# Water_Leak_Detector_PCB.net
KiCad netlist of a schematic drawn in EAGLE
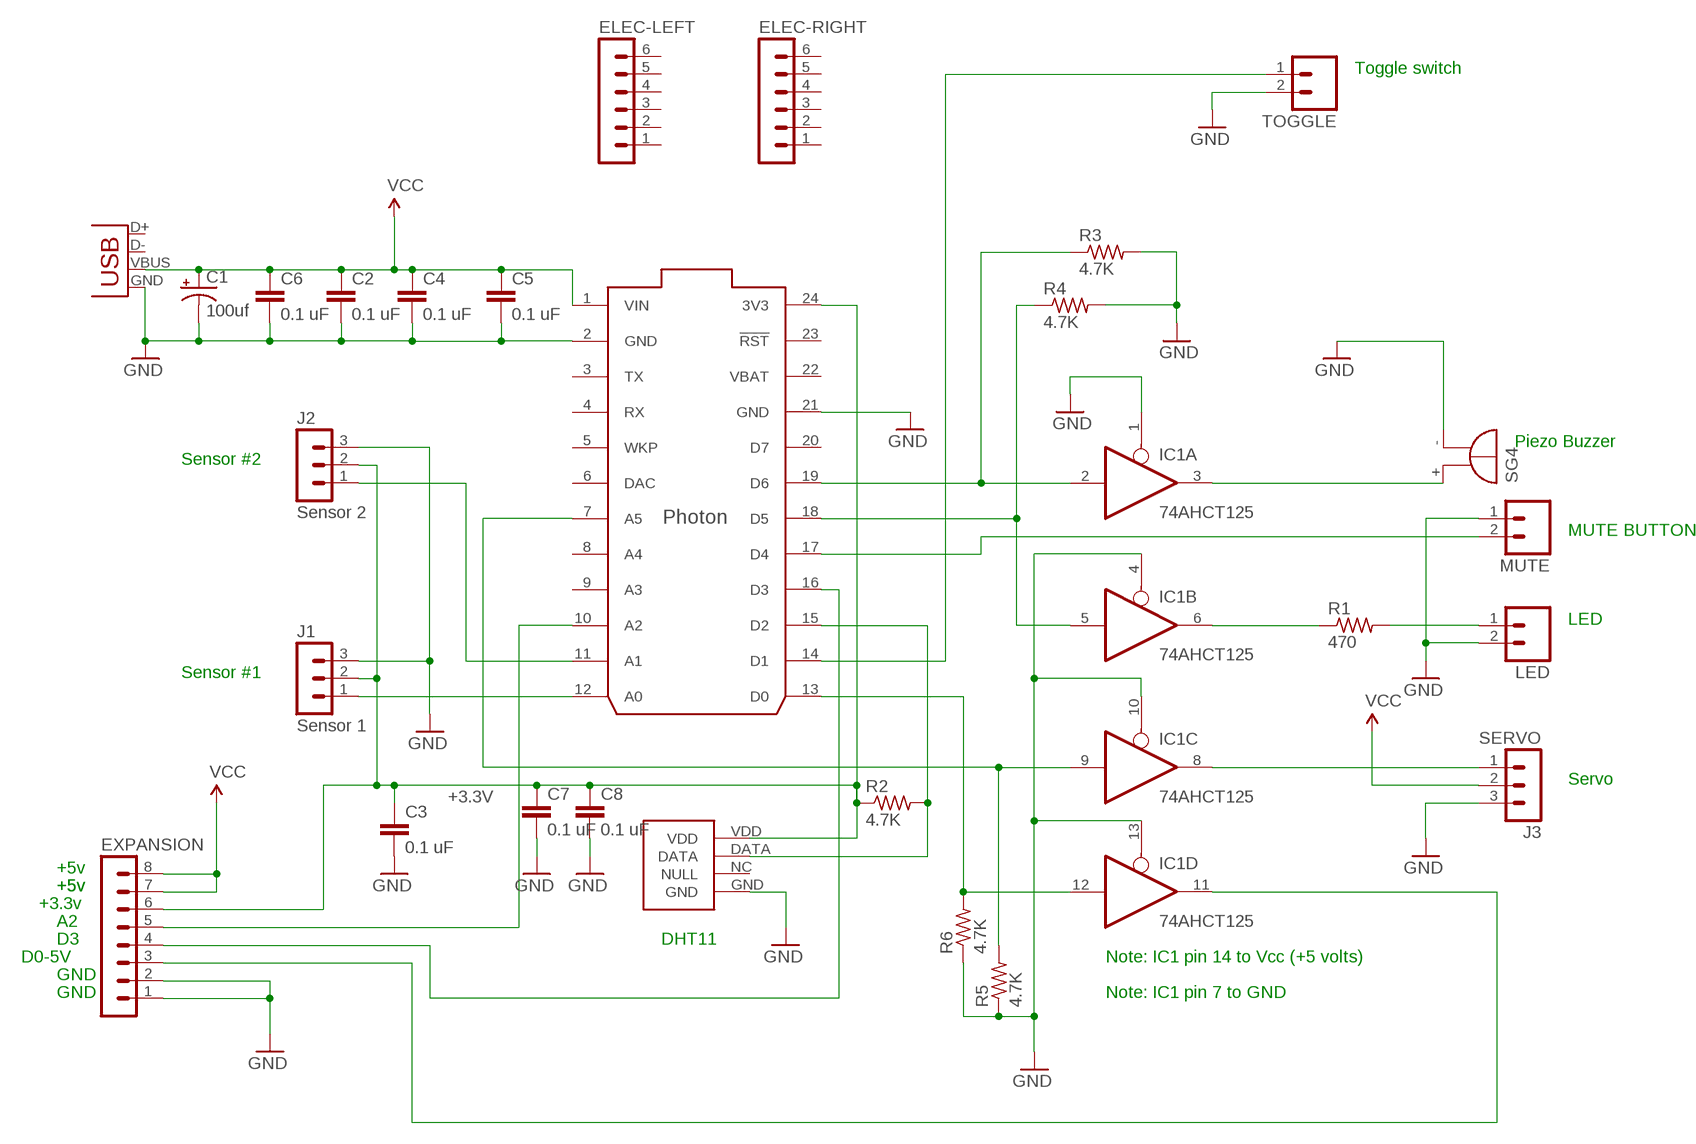
[diagram p0: schematic, sheet 1]

(export (version "E")
  (design (tool "Eeschema 10.0.6"))
  (components
    (comp (ref "C1")
      (value "100uf")
      (footprint "eagle-import:CPOL-RADIAL-100UF-25V")
      (libsource (lib "eagle-import") (part "CAP_POLPTH1"))
    )
    (comp (ref "C2")
      (value "0.1 uF")
      (footprint "eagle-import:CAP-PTH-SMALL")
      (libsource (lib "eagle-import") (part "CAPPTH"))
    )
    (comp (ref "C3")
      (value "0.1 uF")
      (footprint "eagle-import:CAP-PTH-SMALL")
      (libsource (lib "eagle-import") (part "CAPPTH"))
    )
    (comp (ref "C4")
      (value "0.1 uF")
      (footprint "eagle-import:CAP-PTH-SMALL")
      (libsource (lib "eagle-import") (part "CAPPTH"))
    )
    (comp (ref "C5")
      (value "0.1 uF")
      (footprint "eagle-import:CAP-PTH-SMALL")
      (libsource (lib "eagle-import") (part "CAPPTH"))
    )
    (comp (ref "C6")
      (value "0.1 uF")
      (footprint "eagle-import:CAP-PTH-SMALL")
      (libsource (lib "eagle-import") (part "CAPPTH"))
    )
    (comp (ref "C7")
      (value "0.1 uF")
      (footprint "eagle-import:CAP-PTH-SMALL")
      (libsource (lib "eagle-import") (part "CAPPTH"))
    )
    (comp (ref "C8")
      (value "0.1 uF")
      (footprint "eagle-import:CAP-PTH-SMALL")
      (libsource (lib "eagle-import") (part "CAPPTH"))
    )
    (comp (ref "ELEC-LEFT")
      (value "MA06-1")
      (footprint "eagle-import:MA06-1")
      (libsource (lib "eagle-import") (part "MA06-1"))
    )
    (comp (ref "ELEC-RIGHT")
      (value "MA06-1")
      (footprint "eagle-import:MA06-1")
      (libsource (lib "eagle-import") (part "MA06-1"))
    )
    (comp (ref "EXPANSION")
      (value "MA08-1")
      (footprint "eagle-import:MA08-1")
      (libsource (lib "eagle-import") (part "MA08-1"))
    )
    (comp (ref "IC1")
      (value "74AHCT125")
      (footprint "eagle-import:DIL14")
      (libsource (lib "eagle-import") (part "74125N"))
    )
    (comp (ref "J1")
      (value "Sensor 1")
      (footprint "eagle-import:MA03-1")
      (libsource (lib "eagle-import") (part "MA03-1"))
    )
    (comp (ref "J2")
      (value "Sensor 2")
      (footprint "eagle-import:MA03-1")
      (libsource (lib "eagle-import") (part "MA03-1"))
    )
    (comp (ref "J3")
      (value "SERVO")
      (footprint "eagle-import:MA03-1")
      (libsource (lib "eagle-import") (part "MA03-1"))
    )
    (comp (ref "JP1")
      (value "USB-B")
      (footprint "eagle-import:USB-B-PTH")
      (libsource (lib "eagle-import") (part "USBPTH"))
    )
    (comp (ref "LED")
      (value "M02PTH")
      (footprint "eagle-import:1X02")
      (libsource (lib "eagle-import") (part "M02PTH"))
    )
    (comp (ref "MUTE")
      (value "M02PTH")
      (footprint "eagle-import:1X02")
      (libsource (lib "eagle-import") (part "M02PTH"))
    )
    (comp (ref "R1")
      (value "470")
      (footprint "eagle-import:0309_12")
      (libsource (lib "eagle-import") (part "R-US_0309/12"))
    )
    (comp (ref "R2")
      (value "4.7K")
      (footprint "eagle-import:0309_12")
      (libsource (lib "eagle-import") (part "R-US_0309/12"))
    )
    (comp (ref "R3")
      (value "4.7K")
      (footprint "eagle-import:0309_12")
      (libsource (lib "eagle-import") (part "R-US_0309/12"))
    )
    (comp (ref "R4")
      (value "4.7K")
      (footprint "eagle-import:0309_12")
      (libsource (lib "eagle-import") (part "R-US_0309/12"))
    )
    (comp (ref "R5")
      (value "4.7K")
      (footprint "eagle-import:0309_12")
      (libsource (lib "eagle-import") (part "R-US_0309/12"))
    )
    (comp (ref "R6")
      (value "4.7K")
      (footprint "eagle-import:0309_12")
      (libsource (lib "eagle-import") (part "R-US_0309/12"))
    )
    (comp (ref "SG4")
      (value "F/HMB")
      (footprint "eagle-import:F_HMB")
      (libsource (lib "eagle-import") (part "F/HMB"))
    )
    (comp (ref "TOGGLE")
      (value "M02PTH")
      (footprint "eagle-import:1X02")
      (libsource (lib "eagle-import") (part "M02PTH"))
    )
    (comp (ref "U$1")
      (value "PHOTON_WITH_HEADERS")
      (footprint "eagle-import:PHOTON")
      (libsource (lib "eagle-import") (part "PHOTON_WITH_HEADERS"))
    )
    (comp (ref "U$2")
      (value "DHT22")
      (footprint "eagle-import:DHT22")
      (libsource (lib "eagle-import") (part "DHT22"))
    )
  )
  (nets
    (net (code "1") (name "/+3.3V") (class "Default")
      (node (ref "C3") (pin "1") (pinfunction "1_1") (pintype "passive"))
      (node (ref "C7") (pin "1") (pinfunction "1_1") (pintype "passive"))
      (node (ref "C8") (pin "1") (pinfunction "1_1") (pintype "passive"))
      (node (ref "EXPANSION") (pin "6") (pinfunction "6_6") (pintype "passive"))
      (node (ref "J1") (pin "2") (pinfunction "2_2") (pintype "passive"))
      (node (ref "J2") (pin "2") (pinfunction "2_2") (pintype "passive"))
      (node (ref "R2") (pin "1") (pinfunction "1_1") (pintype "passive"))
      (node (ref "U$1") (pin "24") (pinfunction "3V3_24") (pintype "power_in"))
      (node (ref "U$2") (pin "VDD") (pinfunction "VDD_VDD") (pintype "power_in"))
    )
    (net (code "2") (name "/VBAT") (class "Default")
      (node (ref "U$1") (pin "22") (pinfunction "VBAT_22") (pintype "power_in"))
    )
    (net (code "3") (name "GND") (class "Default")
      (node (ref "C1") (pin "2") (pinfunction "-_2") (pintype "passive"))
      (node (ref "C2") (pin "2") (pinfunction "2_2") (pintype "passive"))
      (node (ref "C3") (pin "2") (pinfunction "2_2") (pintype "passive"))
      (node (ref "C4") (pin "2") (pinfunction "2_2") (pintype "passive"))
      (node (ref "C5") (pin "2") (pinfunction "2_2") (pintype "passive"))
      (node (ref "C6") (pin "2") (pinfunction "2_2") (pintype "passive"))
      (node (ref "C7") (pin "2") (pinfunction "2_2") (pintype "passive"))
      (node (ref "C8") (pin "2") (pinfunction "2_2") (pintype "passive"))
      (node (ref "EXPANSION") (pin "1") (pinfunction "1_1") (pintype "passive"))
      (node (ref "EXPANSION") (pin "2") (pinfunction "2_2") (pintype "passive"))
      (node (ref "IC1") (pin "1") (pinfunction "OE_1") (pintype "input"))
      (node (ref "IC1") (pin "10") (pinfunction "OE_10") (pintype "input"))
      (node (ref "IC1") (pin "13") (pinfunction "OE_13") (pintype "input"))
      (node (ref "IC1") (pin "4") (pinfunction "OE_4") (pintype "input"))
      (node (ref "J1") (pin "3") (pinfunction "3_3") (pintype "passive"))
      (node (ref "J2") (pin "3") (pinfunction "3_3") (pintype "passive"))
      (node (ref "J3") (pin "3") (pinfunction "3_3") (pintype "passive"))
      (node (ref "JP1") (pin "GND") (pinfunction "GND_GND") (pintype "bidirectional"))
      (node (ref "LED") (pin "2") (pinfunction "2_2") (pintype "passive"))
      (node (ref "MUTE") (pin "1") (pinfunction "1_1") (pintype "passive"))
      (node (ref "R3") (pin "2") (pinfunction "2_2") (pintype "passive"))
      (node (ref "R4") (pin "2") (pinfunction "2_2") (pintype "passive"))
      (node (ref "R5") (pin "1") (pinfunction "1_1") (pintype "passive"))
      (node (ref "R6") (pin "1") (pinfunction "1_1") (pintype "passive"))
      (node (ref "SG4") (pin "-") (pinfunction "-_-") (pintype "passive"))
      (node (ref "TOGGLE") (pin "2") (pinfunction "2_2") (pintype "passive"))
      (node (ref "U$1") (pin "2") (pinfunction "GND_2") (pintype "power_in"))
      (node (ref "U$1") (pin "21") (pinfunction "GND_21") (pintype "power_in"))
      (node (ref "U$2") (pin "GND") (pinfunction "GND_GND") (pintype "power_in"))
    )
    (net (code "4") (name "Net-(IC1A-I)") (class "Default")
      (node (ref "IC1") (pin "2") (pinfunction "I_2") (pintype "input"))
      (node (ref "R3") (pin "1") (pinfunction "1_1") (pintype "passive"))
      (node (ref "U$1") (pin "19") (pinfunction "D6_19") (pintype "bidirectional"))
    )
    (net (code "5") (name "Net-(IC1A-O)") (class "Default")
      (node (ref "IC1") (pin "3") (pinfunction "O_3") (pintype "tri_state"))
      (node (ref "SG4") (pin "+") (pinfunction "+_+") (pintype "passive"))
    )
    (net (code "6") (name "Net-(IC1B-I)") (class "Default")
      (node (ref "IC1") (pin "5") (pinfunction "I_5") (pintype "input"))
      (node (ref "R4") (pin "1") (pinfunction "1_1") (pintype "passive"))
      (node (ref "U$1") (pin "18") (pinfunction "D5_18") (pintype "bidirectional"))
    )
    (net (code "7") (name "Net-(IC1B-O)") (class "Default")
      (node (ref "IC1") (pin "6") (pinfunction "O_6") (pintype "tri_state"))
      (node (ref "R1") (pin "1") (pinfunction "1_1") (pintype "passive"))
    )
    (net (code "8") (name "Net-(IC1C-I)") (class "Default")
      (node (ref "IC1") (pin "9") (pinfunction "I_9") (pintype "input"))
      (node (ref "R5") (pin "2") (pinfunction "2_2") (pintype "passive"))
      (node (ref "U$1") (pin "7") (pinfunction "A5_7") (pintype "bidirectional"))
    )
    (net (code "9") (name "Net-(IC1C-O)") (class "Default")
      (node (ref "IC1") (pin "8") (pinfunction "O_8") (pintype "tri_state"))
      (node (ref "J3") (pin "1") (pinfunction "1_1") (pintype "passive"))
    )
    (net (code "10") (name "Net-(IC1D-I)") (class "Default")
      (node (ref "IC1") (pin "12") (pinfunction "I_12") (pintype "input"))
      (node (ref "R6") (pin "2") (pinfunction "2_2") (pintype "passive"))
      (node (ref "U$1") (pin "13") (pinfunction "D0_13") (pintype "bidirectional"))
    )
    (net (code "11") (name "Net-(IC1D-O)") (class "Default")
      (node (ref "EXPANSION") (pin "3") (pinfunction "3_3") (pintype "passive"))
      (node (ref "IC1") (pin "11") (pinfunction "O_11") (pintype "tri_state"))
    )
    (net (code "12") (name "Net-(LED-Pad1)") (class "Default")
      (node (ref "LED") (pin "1") (pinfunction "1_1") (pintype "passive"))
      (node (ref "R1") (pin "2") (pinfunction "2_2") (pintype "passive"))
    )
    (net (code "13") (name "Net-(U$1-A0)") (class "Default")
      (node (ref "J1") (pin "1") (pinfunction "1_1") (pintype "passive"))
      (node (ref "U$1") (pin "12") (pinfunction "A0_12") (pintype "bidirectional"))
    )
    (net (code "14") (name "Net-(U$1-A1)") (class "Default")
      (node (ref "J2") (pin "1") (pinfunction "1_1") (pintype "passive"))
      (node (ref "U$1") (pin "11") (pinfunction "A1_11") (pintype "bidirectional"))
    )
    (net (code "15") (name "Net-(U$1-A2)") (class "Default")
      (node (ref "EXPANSION") (pin "5") (pinfunction "5_5") (pintype "passive"))
      (node (ref "U$1") (pin "10") (pinfunction "A2_10") (pintype "bidirectional"))
    )
    (net (code "16") (name "Net-(U$1-D1)") (class "Default")
      (node (ref "TOGGLE") (pin "1") (pinfunction "1_1") (pintype "passive"))
      (node (ref "U$1") (pin "14") (pinfunction "D1_14") (pintype "bidirectional"))
    )
    (net (code "17") (name "Net-(U$1-D2)") (class "Default")
      (node (ref "R2") (pin "2") (pinfunction "2_2") (pintype "passive"))
      (node (ref "U$1") (pin "15") (pinfunction "D2_15") (pintype "bidirectional"))
      (node (ref "U$2") (pin "DATA") (pinfunction "DATA_DATA") (pintype "output"))
    )
    (net (code "18") (name "Net-(U$1-D3)") (class "Default")
      (node (ref "EXPANSION") (pin "4") (pinfunction "4_4") (pintype "passive"))
      (node (ref "U$1") (pin "16") (pinfunction "D3_16") (pintype "bidirectional"))
    )
    (net (code "19") (name "Net-(U$1-D4)") (class "Default")
      (node (ref "MUTE") (pin "2") (pinfunction "2_2") (pintype "passive"))
      (node (ref "U$1") (pin "17") (pinfunction "D4_17") (pintype "bidirectional"))
    )
    (net (code "20") (name "VCC") (class "Default")
      (node (ref "C1") (pin "1") (pinfunction "+_1") (pintype "passive"))
      (node (ref "C2") (pin "1") (pinfunction "1_1") (pintype "passive"))
      (node (ref "C4") (pin "1") (pinfunction "1_1") (pintype "passive"))
      (node (ref "C5") (pin "1") (pinfunction "1_1") (pintype "passive"))
      (node (ref "C6") (pin "1") (pinfunction "1_1") (pintype "passive"))
      (node (ref "EXPANSION") (pin "7") (pinfunction "7_7") (pintype "passive"))
      (node (ref "EXPANSION") (pin "8") (pinfunction "8_8") (pintype "passive"))
      (node (ref "J3") (pin "2") (pinfunction "2_2") (pintype "passive"))
      (node (ref "JP1") (pin "VBUS") (pinfunction "VBUS_VBUS") (pintype "bidirectional"))
      (node (ref "U$1") (pin "1") (pinfunction "VIN_1") (pintype "power_in"))
    )
    (net (code "21") (name "unconnected-(ELEC-LEFT-Pad1)") (class "Default")
      (node (ref "ELEC-LEFT") (pin "1") (pinfunction "1_1") (pintype "passive"))
    )
    (net (code "22") (name "unconnected-(ELEC-LEFT-Pad2)") (class "Default")
      (node (ref "ELEC-LEFT") (pin "2") (pinfunction "2_2") (pintype "passive"))
    )
    (net (code "23") (name "unconnected-(ELEC-LEFT-Pad3)") (class "Default")
      (node (ref "ELEC-LEFT") (pin "3") (pinfunction "3_3") (pintype "passive"))
    )
    (net (code "24") (name "unconnected-(ELEC-LEFT-Pad4)") (class "Default")
      (node (ref "ELEC-LEFT") (pin "4") (pinfunction "4_4") (pintype "passive"))
    )
    (net (code "25") (name "unconnected-(ELEC-LEFT-Pad5)") (class "Default")
      (node (ref "ELEC-LEFT") (pin "5") (pinfunction "5_5") (pintype "passive"))
    )
    (net (code "26") (name "unconnected-(ELEC-LEFT-Pad6)") (class "Default")
      (node (ref "ELEC-LEFT") (pin "6") (pinfunction "6_6") (pintype "passive"))
    )
    (net (code "27") (name "unconnected-(ELEC-RIGHT-Pad1)") (class "Default")
      (node (ref "ELEC-RIGHT") (pin "1") (pinfunction "1_1") (pintype "passive"))
    )
    (net (code "28") (name "unconnected-(ELEC-RIGHT-Pad2)") (class "Default")
      (node (ref "ELEC-RIGHT") (pin "2") (pinfunction "2_2") (pintype "passive"))
    )
    (net (code "29") (name "unconnected-(ELEC-RIGHT-Pad3)") (class "Default")
      (node (ref "ELEC-RIGHT") (pin "3") (pinfunction "3_3") (pintype "passive"))
    )
    (net (code "30") (name "unconnected-(ELEC-RIGHT-Pad4)") (class "Default")
      (node (ref "ELEC-RIGHT") (pin "4") (pinfunction "4_4") (pintype "passive"))
    )
    (net (code "31") (name "unconnected-(ELEC-RIGHT-Pad5)") (class "Default")
      (node (ref "ELEC-RIGHT") (pin "5") (pinfunction "5_5") (pintype "passive"))
    )
    (net (code "32") (name "unconnected-(ELEC-RIGHT-Pad6)") (class "Default")
      (node (ref "ELEC-RIGHT") (pin "6") (pinfunction "6_6") (pintype "passive"))
    )
    (net (code "33") (name "unconnected-(JP1-PadD+)") (class "Default")
      (node (ref "JP1") (pin "D+") (pinfunction "D+_D+") (pintype "bidirectional"))
    )
    (net (code "34") (name "unconnected-(JP1-PadD-)") (class "Default")
      (node (ref "JP1") (pin "D-") (pinfunction "D-_D-") (pintype "bidirectional"))
    )
    (net (code "35") (name "unconnected-(U$1-A3-Pad9)") (class "Default")
      (node (ref "U$1") (pin "9") (pinfunction "A3_9") (pintype "bidirectional"))
    )
    (net (code "36") (name "unconnected-(U$1-A4-Pad8)") (class "Default")
      (node (ref "U$1") (pin "8") (pinfunction "A4_8") (pintype "bidirectional"))
    )
    (net (code "37") (name "unconnected-(U$1-D7-Pad20)") (class "Default")
      (node (ref "U$1") (pin "20") (pinfunction "D7_20") (pintype "bidirectional"))
    )
    (net (code "38") (name "unconnected-(U$1-DAC-Pad6)") (class "Default")
      (node (ref "U$1") (pin "6") (pinfunction "DAC_6") (pintype "bidirectional"))
    )
    (net (code "39") (name "unconnected-(U$1-RX-Pad4)") (class "Default")
      (node (ref "U$1") (pin "4") (pinfunction "RX_4") (pintype "bidirectional"))
    )
    (net (code "40") (name "unconnected-(U$1-TX-Pad3)") (class "Default")
      (node (ref "U$1") (pin "3") (pinfunction "TX_3") (pintype "bidirectional"))
    )
    (net (code "41") (name "unconnected-(U$1-WKP-Pad5)") (class "Default")
      (node (ref "U$1") (pin "5") (pinfunction "WKP_5") (pintype "bidirectional"))
    )
    (net (code "42") (name "unconnected-(U$1-~{RST}-Pad23)") (class "Default")
      (node (ref "U$1") (pin "23") (pinfunction "~{RST}_23") (pintype "bidirectional"))
    )
    (net (code "43") (name "unconnected-(U$2-NULL-PadNC)") (class "Default")
      (node (ref "U$2") (pin "NC") (pinfunction "NULL_NC") (pintype "no_connect"))
    )
  )
)
